# Main.net
KiCad netlist of a schematic drawn in Altium Designer
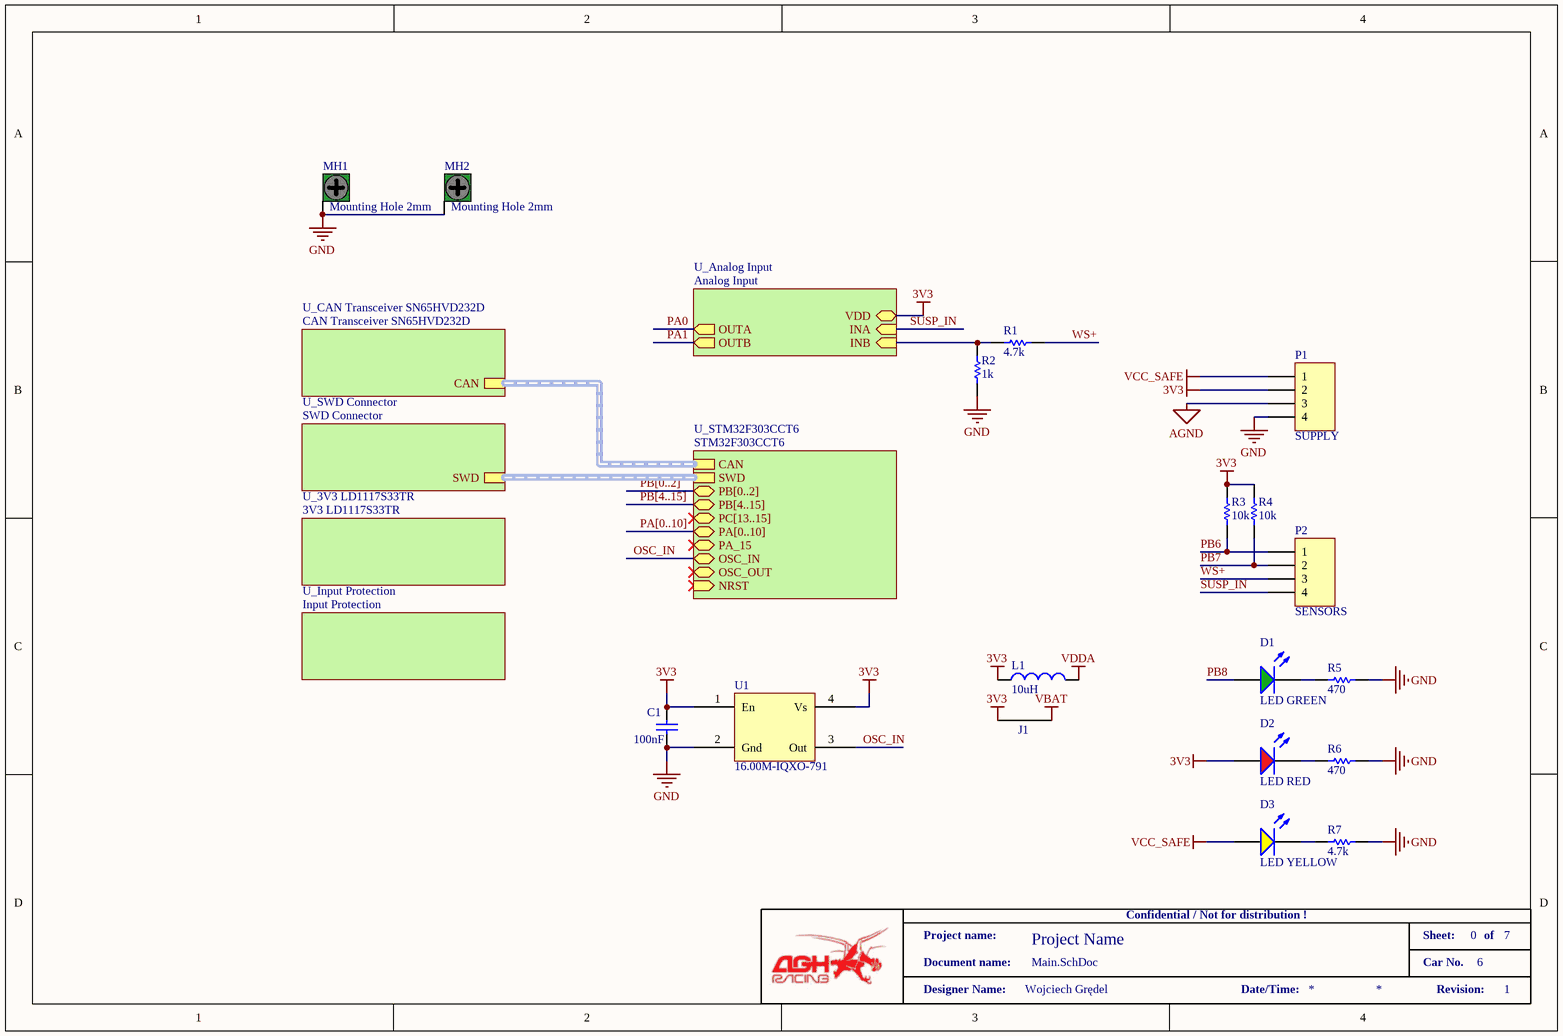
[diagram p0: Main.SchDoc]

(export (version "E")
  (design (tool "Eeschema 10.0.6"))
  (components
    (comp (ref "C1")
      (value "100nF")
      (footprint "agh_racing_2018:CAP_0603_IPC_MD")
      (description "Capacitor")
      (fields (field (name "Comment") "Cap"))
      (libsource (lib "agh_racing_2018") (part "Cap"))
    )
    (comp (ref "D1")
      (value "LED GREEN")
      (footprint "agh_racing_2018:LED_0603_GREEN_IPC_MD")
      (libsource (lib "agh_racing_2018") (part "LED GREEN"))
    )
    (comp (ref "D2")
      (value "LED RED")
      (footprint "agh_racing_2018:LED_0603_RED_IPC_MD")
      (libsource (lib "agh_racing_2018") (part "LED RED"))
    )
    (comp (ref "D3")
      (value "LED YELLOW")
      (footprint "agh_racing_2018:LED_0603_YELLOW_IPC_MD")
      (libsource (lib "agh_racing_2018") (part "LED YELLOW"))
    )
    (comp (ref "J1")
      (value "NetTie")
      (footprint "agh_racing_2018:NETTIE")
      (libsource (lib "agh_racing_2018") (part "NetTie"))
    )
    (comp (ref "L1")
      (value "10uH")
      (footprint "agh_racing_2018:IND_0603_IPC_HD")
      (description "Inductor")
      (fields (field (name "Comment") "Ind"))
      (libsource (lib "agh_racing_2018") (part "Ind"))
    )
    (comp (ref "MH1")
      (value "Mounting Hole 2mm")
      (footprint "agh_racing_2018:MOUNTING HOLE 2mm")
      (libsource (lib "agh_racing_2018") (part "Mounting Hole"))
    )
    (comp (ref "MH2")
      (value "Mounting Hole 2mm")
      (footprint "agh_racing_2018:MOUNTING HOLE 2mm")
      (libsource (lib "agh_racing_2018") (part "Mounting Hole"))
    )
    (comp (ref "P1")
      (value "SUPPLY")
      (footprint "agh_racing_2018:WIRE_PADS_4")
      (description "Header, 4-Pin")
      (libsource (lib "agh_racing_2018") (part "Header 4"))
    )
    (comp (ref "P2")
      (value "SENSORS")
      (footprint "agh_racing_2018:WIRE_PADS_4")
      (description "Header, 4-Pin")
      (libsource (lib "agh_racing_2018") (part "Header 4"))
    )
    (comp (ref "R1")
      (value "4.7k")
      (footprint "agh_racing_2018:RES_0603_IPC_HD")
      (description "Resistor")
      (fields (field (name "Comment") "Res"))
      (libsource (lib "agh_racing_2018") (part "Res"))
    )
    (comp (ref "R2")
      (value "1k")
      (footprint "agh_racing_2018:RES_0603_IPC_HD")
      (description "Resistor")
      (fields (field (name "Comment") "Res"))
      (libsource (lib "agh_racing_2018") (part "Res"))
    )
    (comp (ref "R3")
      (value "10k")
      (footprint "agh_racing_2018:RES_0603_IPC_HD")
      (description "Resistor")
      (fields (field (name "Comment") "Res"))
      (libsource (lib "agh_racing_2018") (part "Res"))
    )
    (comp (ref "R4")
      (value "10k")
      (footprint "agh_racing_2018:RES_0603_IPC_HD")
      (description "Resistor")
      (fields (field (name "Comment") "Res"))
      (libsource (lib "agh_racing_2018") (part "Res"))
    )
    (comp (ref "R5")
      (value "470")
      (footprint "agh_racing_2018:RES_0603_IPC_MD")
      (description "Resistor")
      (fields (field (name "Comment") "Res"))
      (libsource (lib "agh_racing_2018") (part "Res"))
    )
    (comp (ref "R6")
      (value "470")
      (footprint "agh_racing_2018:RES_0603_IPC_MD")
      (description "Resistor")
      (fields (field (name "Comment") "Res"))
      (libsource (lib "agh_racing_2018") (part "Res"))
    )
    (comp (ref "R7")
      (value "4.7k")
      (footprint "agh_racing_2018:RES_0603_IPC_MD")
      (description "Resistor")
      (fields (field (name "Comment") "Res"))
      (libsource (lib "agh_racing_2018") (part "Res"))
    )
    (comp (ref "U1")
      (value "16.00M-IQXO-791")
      (footprint "ICLCX18")
      (description "Crystal Clock Oscillator")
      (fields
        (field (name "MANUFACTURER") "IQD FREQUENCY PRODUCTS")
        (field (name "MPN") "LFSPXO066657CUTT")
        (field (name "NAME") "16.00M-IQXO-791")
      )
      (libsource (lib "agh_racing_2018_temp") (part "16.00M-IQXO-791"))
    )
  )
  (nets
    (net (code "23") (name "/INB") (class "Default")
      (node (ref "R1") (pin "2") (pinfunction "2_2") (pintype "passive"))
      (node (ref "R2") (pin "2") (pinfunction "2_2") (pintype "passive"))
    )
    (net (code "25") (name "/OSC_IN") (class "Default")
      (node (ref "U1") (pin "3") (pinfunction "Out_3") (pintype "passive"))
    )
    (net (code "31") (name "/PB6") (class "Default")
      (node (ref "P2") (pin "1") (pinfunction "1_1") (pintype "passive"))
      (node (ref "R3") (pin "1") (pinfunction "1_1") (pintype "passive"))
    )
    (net (code "32") (name "/PB7") (class "Default")
      (node (ref "P2") (pin "2") (pinfunction "2_2") (pintype "passive"))
      (node (ref "R4") (pin "1") (pinfunction "1_1") (pintype "passive"))
    )
    (net (code "33") (name "/PB8") (class "Default")
      (node (ref "D1") (pin "1") (pinfunction "A_1") (pintype "passive"))
    )
    (net (code "37") (name "/SUSP_IN") (class "Default")
      (node (ref "P2") (pin "4") (pinfunction "4_4") (pintype "passive"))
    )
    (net (code "39") (name "/WS+") (class "Default")
      (node (ref "P2") (pin "3") (pinfunction "3_3") (pintype "passive"))
      (node (ref "R1") (pin "1") (pinfunction "1_1") (pintype "passive"))
    )
    (net (code "40") (name "3V3") (class "Default")
      (node (ref "C1") (pin "2") (pinfunction "2_2") (pintype "passive"))
      (node (ref "D2") (pin "1") (pinfunction "A_1") (pintype "passive"))
      (node (ref "J1") (pin "1") (pinfunction "1_1") (pintype "passive"))
      (node (ref "L1") (pin "1") (pinfunction "1_1") (pintype "passive"))
      (node (ref "P1") (pin "2") (pinfunction "2_2") (pintype "passive"))
      (node (ref "R3") (pin "2") (pinfunction "2_2") (pintype "passive"))
      (node (ref "R4") (pin "2") (pinfunction "2_2") (pintype "passive"))
      (node (ref "U1") (pin "1") (pinfunction "En_1") (pintype "passive"))
      (node (ref "U1") (pin "4") (pinfunction "Vs_4") (pintype "passive"))
    )
    (net (code "41") (name "AGND") (class "Default")
      (node (ref "P1") (pin "3") (pinfunction "3_3") (pintype "passive"))
    )
    (net (code "42") (name "GND") (class "Default")
      (node (ref "C1") (pin "1") (pinfunction "1_1") (pintype "passive"))
      (node (ref "MH1") (pin "MOUNTING") (pinfunction "MOUNTING_MOUNTING") (pintype "passive"))
      (node (ref "MH2") (pin "MOUNTING") (pinfunction "MOUNTING_MOUNTING") (pintype "passive"))
      (node (ref "P1") (pin "4") (pinfunction "4_4") (pintype "passive"))
      (node (ref "R2") (pin "1") (pinfunction "1_1") (pintype "passive"))
      (node (ref "R5") (pin "1") (pinfunction "1_1") (pintype "passive"))
      (node (ref "R6") (pin "1") (pinfunction "1_1") (pintype "passive"))
      (node (ref "R7") (pin "1") (pinfunction "1_1") (pintype "passive"))
      (node (ref "U1") (pin "2") (pinfunction "Gnd_2") (pintype "passive"))
    )
    (net (code "43") (name "Net-(D1-K)") (class "Default")
      (node (ref "D1") (pin "2") (pinfunction "K_2") (pintype "passive"))
      (node (ref "R5") (pin "2") (pinfunction "2_2") (pintype "passive"))
    )
    (net (code "44") (name "Net-(D2-K)") (class "Default")
      (node (ref "D2") (pin "2") (pinfunction "K_2") (pintype "passive"))
      (node (ref "R6") (pin "2") (pinfunction "2_2") (pintype "passive"))
    )
    (net (code "45") (name "Net-(D3-K)") (class "Default")
      (node (ref "D3") (pin "2") (pinfunction "K_2") (pintype "passive"))
      (node (ref "R7") (pin "2") (pinfunction "2_2") (pintype "passive"))
    )
    (net (code "46") (name "VBAT") (class "Default")
      (node (ref "J1") (pin "2") (pinfunction "2_2") (pintype "passive"))
    )
    (net (code "47") (name "VCC_SAFE") (class "Default")
      (node (ref "D3") (pin "1") (pinfunction "A_1") (pintype "passive"))
      (node (ref "P1") (pin "1") (pinfunction "1_1") (pintype "passive"))
    )
    (net (code "48") (name "VDDA") (class "Default")
      (node (ref "L1") (pin "2") (pinfunction "2_2") (pintype "passive"))
    )
  )
)
